# reset-switch.net
KiCad netlist of a schematic drawn in Altium Designer
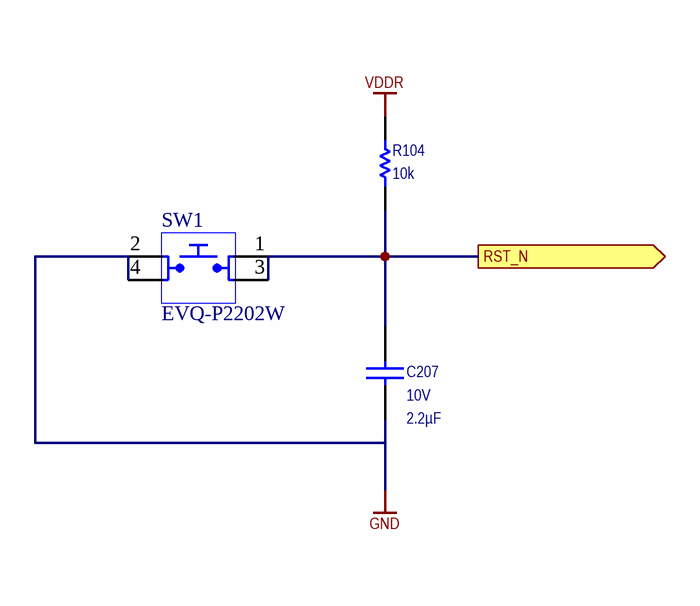
[diagram p0: reset-switch.SchDoc]

(export (version "E")
  (design (tool "Eeschema 10.0.6"))
  (components
    (comp (ref "C207")
      (value "GRM188R71A225KE15D")
      (footprint "CAPC1608X90N")
      (description "CAP CER 2.2UF 10V 10% X7R 0603")
      (fields
        (field (name "MANUFACTURER") "Murata Electronics North America")
        (field (name "TOLERANCE") "±10%")
        (field (name "VOLTAGE - RATED") "10V")
        (field (name "CAPACITANCE") "2.2µF")
      )
      (libsource (lib "murata") (part "GRM188R71A225KE15D"))
    )
    (comp (ref "R104")
      (value "10k")
      (footprint "0603")
      (description "Thick Film Resistor 10k Ohms +/-1% 0.1W SMD 0603")
      (fields (field (name "TOLERANCE") "+/-1%") (field (name "MANUFACTURER") "Panasonic - ECG"))
      (libsource (lib "brinton") (part "RES"))
    )
    (comp (ref "SW1")
      (value "EVQ-P2202W")
      (footprint "EVQP2-2.5")
      (description "Switch Tact SPST-NO 4.7x3.5mm SMT")
      (fields (field (name "MFG") "Panasonic"))
      (libsource (lib "Kron Library Rev 3") (part "EVQ-P2202W"))
    )
  )
  (nets
    (net (code "1") (name "/RST_N") (class "Default")
      (node (ref "C207") (pin "2") (pinfunction "2_2") (pintype "passive"))
      (node (ref "R104") (pin "1") (pinfunction "1_1") (pintype "passive"))
      (node (ref "SW1") (pin "1") (pinfunction "1_1") (pintype "passive"))
      (node (ref "SW1") (pin "3") (pinfunction "3_3") (pintype "passive"))
    )
    (net (code "2") (name "GND") (class "Default")
      (node (ref "C207") (pin "1") (pinfunction "1_1") (pintype "passive"))
      (node (ref "SW1") (pin "2") (pinfunction "2_2") (pintype "passive"))
      (node (ref "SW1") (pin "4") (pinfunction "4_4") (pintype "passive"))
    )
    (net (code "3") (name "VDDR") (class "Default")
      (node (ref "R104") (pin "2") (pinfunction "2_2") (pintype "passive"))
    )
  )
)
